# RPi_RGB_Matrix.net
KiCad netlist of a schematic drawn in EAGLE
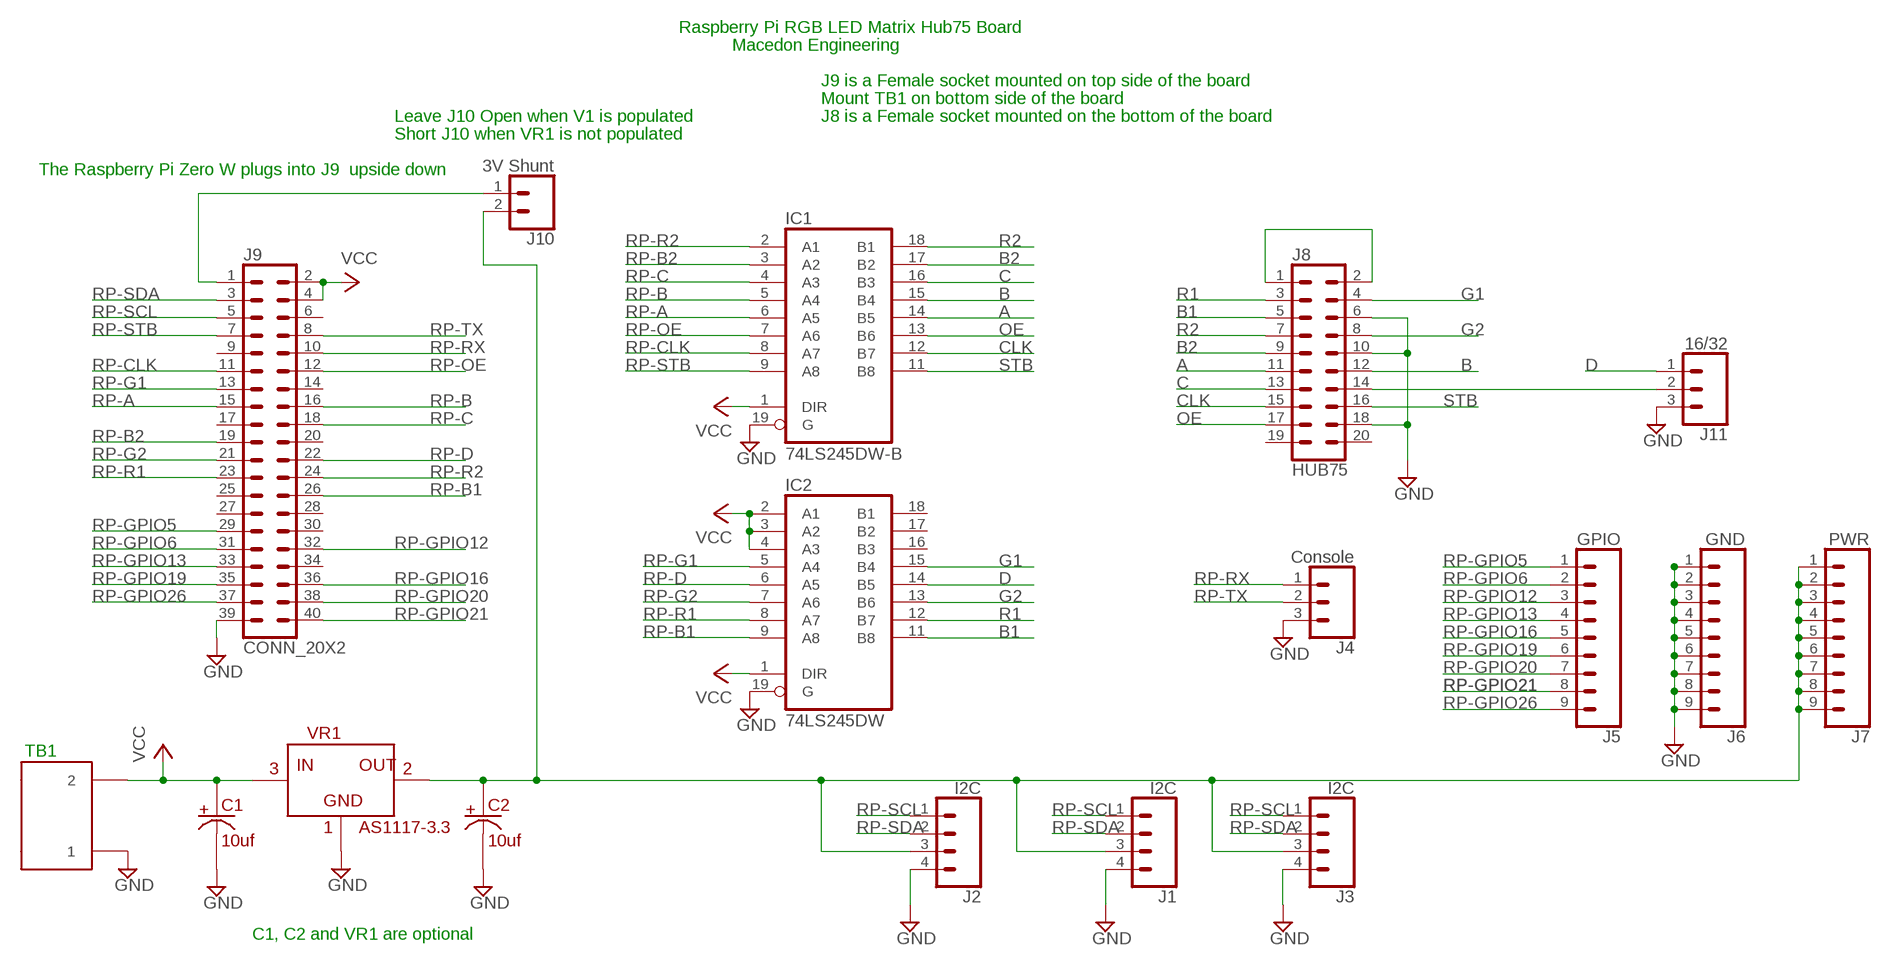
[diagram p0: schematic, sheet 1]

(export (version "E")
  (design (tool "Eeschema 10.0.6"))
  (components
    (comp (ref "C1")
      (value "10uf")
      (footprint "eagle-import:CAP-SMT-A")
      (libsource (lib "eagle-import") (part "CAP-POL-SMT-A{dblquote}"))
    )
    (comp (ref "C2")
      (value "10uf")
      (footprint "eagle-import:CAP-SMT-A")
      (libsource (lib "eagle-import") (part "CAP-POL-SMT-A{dblquote}"))
    )
    (comp (ref "IC1")
      (value "74LS245DW-B")
      (footprint "eagle-import:SO20W-B")
      (libsource (lib "eagle-import") (part "74245DW-BLS"))
    )
    (comp (ref "IC2")
      (value "74LS245DW")
      (footprint "eagle-import:SO20W")
      (libsource (lib "eagle-import") (part "74245DWLS"))
    )
    (comp (ref "J1")
      (value "I2C")
      (footprint "eagle-import:1X04")
      (libsource (lib "eagle-import") (part "CONN_04"))
    )
    (comp (ref "J2")
      (value "I2C")
      (footprint "eagle-import:1X04")
      (libsource (lib "eagle-import") (part "CONN_04"))
    )
    (comp (ref "J3")
      (value "I2C")
      (footprint "eagle-import:1X04")
      (libsource (lib "eagle-import") (part "CONN_04"))
    )
    (comp (ref "J4")
      (value "Console")
      (footprint "eagle-import:1X03")
      (libsource (lib "eagle-import") (part "CONN_03"))
    )
    (comp (ref "J5")
      (value "GPIO")
      (footprint "eagle-import:1X09")
      (libsource (lib "eagle-import") (part "CONN_09"))
    )
    (comp (ref "J6")
      (value "GND")
      (footprint "eagle-import:1X09")
      (libsource (lib "eagle-import") (part "CONN_09"))
    )
    (comp (ref "J7")
      (value "PWR")
      (footprint "eagle-import:1X09")
      (libsource (lib "eagle-import") (part "CONN_09"))
    )
    (comp (ref "J8")
      (value "HUB75")
      (footprint "eagle-import:2X10")
      (libsource (lib "eagle-import") (part "CONN_10X2"))
    )
    (comp (ref "J9")
      (value "CONN_20X2")
      (footprint "eagle-import:2X20")
      (libsource (lib "eagle-import") (part "CONN_20X2"))
    )
    (comp (ref "J10")
      (value "3V Shunt")
      (footprint "eagle-import:1X02")
      (libsource (lib "eagle-import") (part "CONN_02"))
    )
    (comp (ref "J11")
      (value "16/32")
      (footprint "eagle-import:1X03")
      (libsource (lib "eagle-import") (part "CONN_03"))
    )
    (comp (ref "TB1")
      (value "TERMINALBLOCK-5MM-2POS")
      (footprint "eagle-import:TERMINALBLOCK-5MM-2POS")
      (libsource (lib "eagle-import") (part "TERMINALBLOCK-5MM-2POS"))
    )
    (comp (ref "VR1")
      (value "AS1117-3.3")
      (footprint "eagle-import:SOT-223")
      (libsource (lib "eagle-import") (part "AS1117"))
    )
  )
  (nets
    (net (code "1") (name "/A") (class "Default")
      (node (ref "IC1") (pin "14") (pinfunction "B5_14") (pintype "bidirectional"))
      (node (ref "J8") (pin "11") (pinfunction "11_11") (pintype "passive"))
    )
    (net (code "2") (name "/B") (class "Default")
      (node (ref "IC1") (pin "15") (pinfunction "B4_15") (pintype "bidirectional"))
      (node (ref "J8") (pin "12") (pinfunction "12_12") (pintype "passive"))
    )
    (net (code "3") (name "/B1") (class "Default")
      (node (ref "IC2") (pin "11") (pinfunction "B8_11") (pintype "bidirectional"))
      (node (ref "J8") (pin "5") (pinfunction "5_5") (pintype "passive"))
    )
    (net (code "4") (name "/B2") (class "Default")
      (node (ref "IC1") (pin "17") (pinfunction "B2_17") (pintype "bidirectional"))
      (node (ref "J8") (pin "9") (pinfunction "9_9") (pintype "passive"))
    )
    (net (code "5") (name "/C") (class "Default")
      (node (ref "IC1") (pin "16") (pinfunction "B3_16") (pintype "bidirectional"))
      (node (ref "J8") (pin "13") (pinfunction "13_13") (pintype "passive"))
    )
    (net (code "6") (name "/CLK") (class "Default")
      (node (ref "IC1") (pin "12") (pinfunction "B7_12") (pintype "bidirectional"))
      (node (ref "J8") (pin "15") (pinfunction "15_15") (pintype "passive"))
    )
    (net (code "7") (name "/D") (class "Default")
      (node (ref "IC2") (pin "14") (pinfunction "B5_14") (pintype "bidirectional"))
      (node (ref "J11") (pin "1") (pinfunction "1_1") (pintype "passive"))
    )
    (net (code "8") (name "/G1") (class "Default")
      (node (ref "IC2") (pin "15") (pinfunction "B4_15") (pintype "bidirectional"))
      (node (ref "J8") (pin "4") (pinfunction "4_4") (pintype "passive"))
    )
    (net (code "9") (name "/G2") (class "Default")
      (node (ref "IC2") (pin "13") (pinfunction "B6_13") (pintype "bidirectional"))
      (node (ref "J8") (pin "8") (pinfunction "8_8") (pintype "passive"))
    )
    (net (code "10") (name "/OE") (class "Default")
      (node (ref "IC1") (pin "13") (pinfunction "B6_13") (pintype "bidirectional"))
      (node (ref "J8") (pin "17") (pinfunction "17_17") (pintype "passive"))
    )
    (net (code "11") (name "/R1") (class "Default")
      (node (ref "IC2") (pin "12") (pinfunction "B7_12") (pintype "bidirectional"))
      (node (ref "J8") (pin "3") (pinfunction "3_3") (pintype "passive"))
    )
    (net (code "12") (name "/R2") (class "Default")
      (node (ref "IC1") (pin "18") (pinfunction "B1_18") (pintype "bidirectional"))
      (node (ref "J8") (pin "7") (pinfunction "7_7") (pintype "passive"))
    )
    (net (code "13") (name "/RP-A") (class "Default")
      (node (ref "IC1") (pin "6") (pinfunction "A5_6") (pintype "bidirectional"))
      (node (ref "J9") (pin "15") (pinfunction "15_15") (pintype "passive"))
    )
    (net (code "14") (name "/RP-B") (class "Default")
      (node (ref "IC1") (pin "5") (pinfunction "A4_5") (pintype "bidirectional"))
      (node (ref "J9") (pin "16") (pinfunction "16_16") (pintype "passive"))
    )
    (net (code "15") (name "/RP-B1") (class "Default")
      (node (ref "IC2") (pin "9") (pinfunction "A8_9") (pintype "bidirectional"))
      (node (ref "J9") (pin "26") (pinfunction "26_26") (pintype "passive"))
    )
    (net (code "16") (name "/RP-B2") (class "Default")
      (node (ref "IC1") (pin "3") (pinfunction "A2_3") (pintype "bidirectional"))
      (node (ref "J9") (pin "19") (pinfunction "19_19") (pintype "passive"))
    )
    (net (code "17") (name "/RP-C") (class "Default")
      (node (ref "IC1") (pin "4") (pinfunction "A3_4") (pintype "bidirectional"))
      (node (ref "J9") (pin "18") (pinfunction "18_18") (pintype "passive"))
    )
    (net (code "18") (name "/RP-CLK") (class "Default")
      (node (ref "IC1") (pin "8") (pinfunction "A7_8") (pintype "bidirectional"))
      (node (ref "J9") (pin "11") (pinfunction "11_11") (pintype "passive"))
    )
    (net (code "19") (name "/RP-D") (class "Default")
      (node (ref "IC2") (pin "6") (pinfunction "A5_6") (pintype "bidirectional"))
      (node (ref "J9") (pin "22") (pinfunction "22_22") (pintype "passive"))
    )
    (net (code "20") (name "/RP-G1") (class "Default")
      (node (ref "IC2") (pin "5") (pinfunction "A4_5") (pintype "bidirectional"))
      (node (ref "J9") (pin "13") (pinfunction "13_13") (pintype "passive"))
    )
    (net (code "21") (name "/RP-G2") (class "Default")
      (node (ref "IC2") (pin "7") (pinfunction "A6_7") (pintype "bidirectional"))
      (node (ref "J9") (pin "21") (pinfunction "21_21") (pintype "passive"))
    )
    (net (code "22") (name "/RP-GPIO5") (class "Default")
      (node (ref "J5") (pin "1") (pinfunction "1_1") (pintype "passive"))
      (node (ref "J9") (pin "29") (pinfunction "29_29") (pintype "passive"))
    )
    (net (code "23") (name "/RP-GPIO6") (class "Default")
      (node (ref "J5") (pin "2") (pinfunction "2_2") (pintype "passive"))
      (node (ref "J9") (pin "31") (pinfunction "31_31") (pintype "passive"))
    )
    (net (code "24") (name "/RP-GPIO12") (class "Default")
      (node (ref "J5") (pin "3") (pinfunction "3_3") (pintype "passive"))
      (node (ref "J9") (pin "32") (pinfunction "32_32") (pintype "passive"))
    )
    (net (code "25") (name "/RP-GPIO13") (class "Default")
      (node (ref "J5") (pin "4") (pinfunction "4_4") (pintype "passive"))
      (node (ref "J9") (pin "33") (pinfunction "33_33") (pintype "passive"))
    )
    (net (code "26") (name "/RP-GPIO16") (class "Default")
      (node (ref "J5") (pin "5") (pinfunction "5_5") (pintype "passive"))
      (node (ref "J9") (pin "36") (pinfunction "36_36") (pintype "passive"))
    )
    (net (code "27") (name "/RP-GPIO19") (class "Default")
      (node (ref "J5") (pin "6") (pinfunction "6_6") (pintype "passive"))
      (node (ref "J9") (pin "35") (pinfunction "35_35") (pintype "passive"))
    )
    (net (code "28") (name "/RP-GPIO20") (class "Default")
      (node (ref "J5") (pin "7") (pinfunction "7_7") (pintype "passive"))
      (node (ref "J9") (pin "38") (pinfunction "38_38") (pintype "passive"))
    )
    (net (code "29") (name "/RP-GPIO21") (class "Default")
      (node (ref "J5") (pin "8") (pinfunction "8_8") (pintype "passive"))
      (node (ref "J9") (pin "40") (pinfunction "40_40") (pintype "passive"))
    )
    (net (code "30") (name "/RP-GPIO26") (class "Default")
      (node (ref "J5") (pin "9") (pinfunction "9_9") (pintype "passive"))
      (node (ref "J9") (pin "37") (pinfunction "37_37") (pintype "passive"))
    )
    (net (code "31") (name "/RP-OE") (class "Default")
      (node (ref "IC1") (pin "7") (pinfunction "A6_7") (pintype "bidirectional"))
      (node (ref "J9") (pin "12") (pinfunction "12_12") (pintype "passive"))
    )
    (net (code "32") (name "/RP-R1") (class "Default")
      (node (ref "IC2") (pin "8") (pinfunction "A7_8") (pintype "bidirectional"))
      (node (ref "J9") (pin "23") (pinfunction "23_23") (pintype "passive"))
    )
    (net (code "33") (name "/RP-R2") (class "Default")
      (node (ref "IC1") (pin "2") (pinfunction "A1_2") (pintype "bidirectional"))
      (node (ref "J9") (pin "24") (pinfunction "24_24") (pintype "passive"))
    )
    (net (code "34") (name "/RP-RX") (class "Default")
      (node (ref "J4") (pin "1") (pinfunction "1_1") (pintype "passive"))
      (node (ref "J9") (pin "10") (pinfunction "10_10") (pintype "passive"))
    )
    (net (code "35") (name "/RP-SCL") (class "Default")
      (node (ref "J1") (pin "1") (pinfunction "1_1") (pintype "passive"))
      (node (ref "J2") (pin "1") (pinfunction "1_1") (pintype "passive"))
      (node (ref "J3") (pin "1") (pinfunction "1_1") (pintype "passive"))
      (node (ref "J9") (pin "5") (pinfunction "5_5") (pintype "passive"))
    )
    (net (code "36") (name "/RP-SDA") (class "Default")
      (node (ref "J1") (pin "2") (pinfunction "2_2") (pintype "passive"))
      (node (ref "J2") (pin "2") (pinfunction "2_2") (pintype "passive"))
      (node (ref "J3") (pin "2") (pinfunction "2_2") (pintype "passive"))
      (node (ref "J9") (pin "3") (pinfunction "3_3") (pintype "passive"))
    )
    (net (code "37") (name "/RP-STB") (class "Default")
      (node (ref "IC1") (pin "9") (pinfunction "A8_9") (pintype "bidirectional"))
      (node (ref "J9") (pin "7") (pinfunction "7_7") (pintype "passive"))
    )
    (net (code "38") (name "/RP-TX") (class "Default")
      (node (ref "J4") (pin "2") (pinfunction "2_2") (pintype "passive"))
      (node (ref "J9") (pin "8") (pinfunction "8_8") (pintype "passive"))
    )
    (net (code "39") (name "/STB") (class "Default")
      (node (ref "IC1") (pin "11") (pinfunction "B8_11") (pintype "bidirectional"))
      (node (ref "J8") (pin "16") (pinfunction "16_16") (pintype "passive"))
    )
    (net (code "40") (name "GND") (class "Default")
      (node (ref "C1") (pin "P$2") (pinfunction "P$2_P$2") (pintype "passive"))
      (node (ref "C2") (pin "P$2") (pinfunction "P$2_P$2") (pintype "passive"))
      (node (ref "IC1") (pin "19") (pinfunction "G_19") (pintype "input"))
      (node (ref "IC2") (pin "19") (pinfunction "G_19") (pintype "input"))
      (node (ref "J1") (pin "4") (pinfunction "4_4") (pintype "passive"))
      (node (ref "J11") (pin "3") (pinfunction "3_3") (pintype "passive"))
      (node (ref "J2") (pin "4") (pinfunction "4_4") (pintype "passive"))
      (node (ref "J3") (pin "4") (pinfunction "4_4") (pintype "passive"))
      (node (ref "J4") (pin "3") (pinfunction "3_3") (pintype "passive"))
      (node (ref "J6") (pin "1") (pinfunction "1_1") (pintype "passive"))
      (node (ref "J6") (pin "2") (pinfunction "2_2") (pintype "passive"))
      (node (ref "J6") (pin "3") (pinfunction "3_3") (pintype "passive"))
      (node (ref "J6") (pin "4") (pinfunction "4_4") (pintype "passive"))
      (node (ref "J6") (pin "5") (pinfunction "5_5") (pintype "passive"))
      (node (ref "J6") (pin "6") (pinfunction "6_6") (pintype "passive"))
      (node (ref "J6") (pin "7") (pinfunction "7_7") (pintype "passive"))
      (node (ref "J6") (pin "8") (pinfunction "8_8") (pintype "passive"))
      (node (ref "J6") (pin "9") (pinfunction "9_9") (pintype "passive"))
      (node (ref "J8") (pin "10") (pinfunction "10_10") (pintype "passive"))
      (node (ref "J8") (pin "18") (pinfunction "18_18") (pintype "passive"))
      (node (ref "J8") (pin "6") (pinfunction "6_6") (pintype "passive"))
      (node (ref "J9") (pin "39") (pinfunction "39_39") (pintype "passive"))
      (node (ref "TB1") (pin "P$1") (pinfunction "1_P$1") (pintype "bidirectional"))
      (node (ref "TB1") (pin "P$4") (pinfunction "1_P$4") (pintype "bidirectional"))
      (node (ref "VR1") (pin "P$1") (pinfunction "P$1_P$1") (pintype "bidirectional"))
    )
    (net (code "41") (name "Net-(C2-PadP$1)") (class "Default")
      (node (ref "C2") (pin "P$1") (pinfunction "P$1_P$1") (pintype "passive"))
      (node (ref "J1") (pin "3") (pinfunction "3_3") (pintype "passive"))
      (node (ref "J10") (pin "2") (pinfunction "2_2") (pintype "passive"))
      (node (ref "J2") (pin "3") (pinfunction "3_3") (pintype "passive"))
      (node (ref "J3") (pin "3") (pinfunction "3_3") (pintype "passive"))
      (node (ref "J7") (pin "1") (pinfunction "1_1") (pintype "passive"))
      (node (ref "J7") (pin "2") (pinfunction "2_2") (pintype "passive"))
      (node (ref "J7") (pin "3") (pinfunction "3_3") (pintype "passive"))
      (node (ref "J7") (pin "4") (pinfunction "4_4") (pintype "passive"))
      (node (ref "J7") (pin "5") (pinfunction "5_5") (pintype "passive"))
      (node (ref "J7") (pin "6") (pinfunction "6_6") (pintype "passive"))
      (node (ref "J7") (pin "7") (pinfunction "7_7") (pintype "passive"))
      (node (ref "J7") (pin "8") (pinfunction "8_8") (pintype "passive"))
      (node (ref "J7") (pin "9") (pinfunction "9_9") (pintype "passive"))
      (node (ref "VR1") (pin "P$2") (pinfunction "P$2_P$2") (pintype "bidirectional"))
      (node (ref "VR1") (pin "P$4") (pinfunction "P$2_P$4") (pintype "bidirectional"))
    )
    (net (code "42") (name "Net-(J8-Pad1)") (class "Default")
      (node (ref "J8") (pin "1") (pinfunction "1_1") (pintype "passive"))
      (node (ref "J8") (pin "2") (pinfunction "2_2") (pintype "passive"))
    )
    (net (code "43") (name "Net-(J10-Pad1)") (class "Default")
      (node (ref "J10") (pin "1") (pinfunction "1_1") (pintype "passive"))
      (node (ref "J9") (pin "1") (pinfunction "1_1") (pintype "passive"))
    )
    (net (code "44") (name "Net-(J11-Pad2)") (class "Default")
      (node (ref "J11") (pin "2") (pinfunction "2_2") (pintype "passive"))
      (node (ref "J8") (pin "14") (pinfunction "14_14") (pintype "passive"))
    )
    (net (code "45") (name "VCC") (class "Default")
      (node (ref "C1") (pin "P$1") (pinfunction "P$1_P$1") (pintype "passive"))
      (node (ref "IC1") (pin "1") (pinfunction "DIR_1") (pintype "input"))
      (node (ref "IC2") (pin "1") (pinfunction "DIR_1") (pintype "input"))
      (node (ref "IC2") (pin "2") (pinfunction "A1_2") (pintype "bidirectional"))
      (node (ref "IC2") (pin "3") (pinfunction "A2_3") (pintype "bidirectional"))
      (node (ref "IC2") (pin "4") (pinfunction "A3_4") (pintype "bidirectional"))
      (node (ref "J9") (pin "2") (pinfunction "2_2") (pintype "passive"))
      (node (ref "J9") (pin "4") (pinfunction "4_4") (pintype "passive"))
      (node (ref "TB1") (pin "P$2") (pinfunction "2_P$2") (pintype "bidirectional"))
      (node (ref "TB1") (pin "P$3") (pinfunction "2_P$3") (pintype "bidirectional"))
      (node (ref "VR1") (pin "P$3") (pinfunction "P$3_P$3") (pintype "bidirectional"))
    )
    (net (code "46") (name "unconnected-(IC2A-B1-Pad18)") (class "Default")
      (node (ref "IC2") (pin "18") (pinfunction "B1_18") (pintype "bidirectional"))
    )
    (net (code "47") (name "unconnected-(IC2A-B2-Pad17)") (class "Default")
      (node (ref "IC2") (pin "17") (pinfunction "B2_17") (pintype "bidirectional"))
    )
    (net (code "48") (name "unconnected-(IC2A-B3-Pad16)") (class "Default")
      (node (ref "IC2") (pin "16") (pinfunction "B3_16") (pintype "bidirectional"))
    )
    (net (code "49") (name "unconnected-(J8-Pad19)") (class "Default")
      (node (ref "J8") (pin "19") (pinfunction "19_19") (pintype "passive"))
    )
    (net (code "50") (name "unconnected-(J8-Pad20)") (class "Default")
      (node (ref "J8") (pin "20") (pinfunction "20_20") (pintype "passive"))
    )
    (net (code "51") (name "unconnected-(J9-Pad6)") (class "Default")
      (node (ref "J9") (pin "6") (pinfunction "6_6") (pintype "passive"))
    )
    (net (code "52") (name "unconnected-(J9-Pad9)") (class "Default")
      (node (ref "J9") (pin "9") (pinfunction "9_9") (pintype "passive"))
    )
    (net (code "53") (name "unconnected-(J9-Pad14)") (class "Default")
      (node (ref "J9") (pin "14") (pinfunction "14_14") (pintype "passive"))
    )
    (net (code "54") (name "unconnected-(J9-Pad17)") (class "Default")
      (node (ref "J9") (pin "17") (pinfunction "17_17") (pintype "passive"))
    )
    (net (code "55") (name "unconnected-(J9-Pad20)") (class "Default")
      (node (ref "J9") (pin "20") (pinfunction "20_20") (pintype "passive"))
    )
    (net (code "56") (name "unconnected-(J9-Pad25)") (class "Default")
      (node (ref "J9") (pin "25") (pinfunction "25_25") (pintype "passive"))
    )
    (net (code "57") (name "unconnected-(J9-Pad27)") (class "Default")
      (node (ref "J9") (pin "27") (pinfunction "27_27") (pintype "passive"))
    )
    (net (code "58") (name "unconnected-(J9-Pad28)") (class "Default")
      (node (ref "J9") (pin "28") (pinfunction "28_28") (pintype "passive"))
    )
    (net (code "59") (name "unconnected-(J9-Pad30)") (class "Default")
      (node (ref "J9") (pin "30") (pinfunction "30_30") (pintype "passive"))
    )
    (net (code "60") (name "unconnected-(J9-Pad34)") (class "Default")
      (node (ref "J9") (pin "34") (pinfunction "34_34") (pintype "passive"))
    )
  )
)
